# EncoderArm.net
KiCad netlist of a schematic drawn in Altium Designer
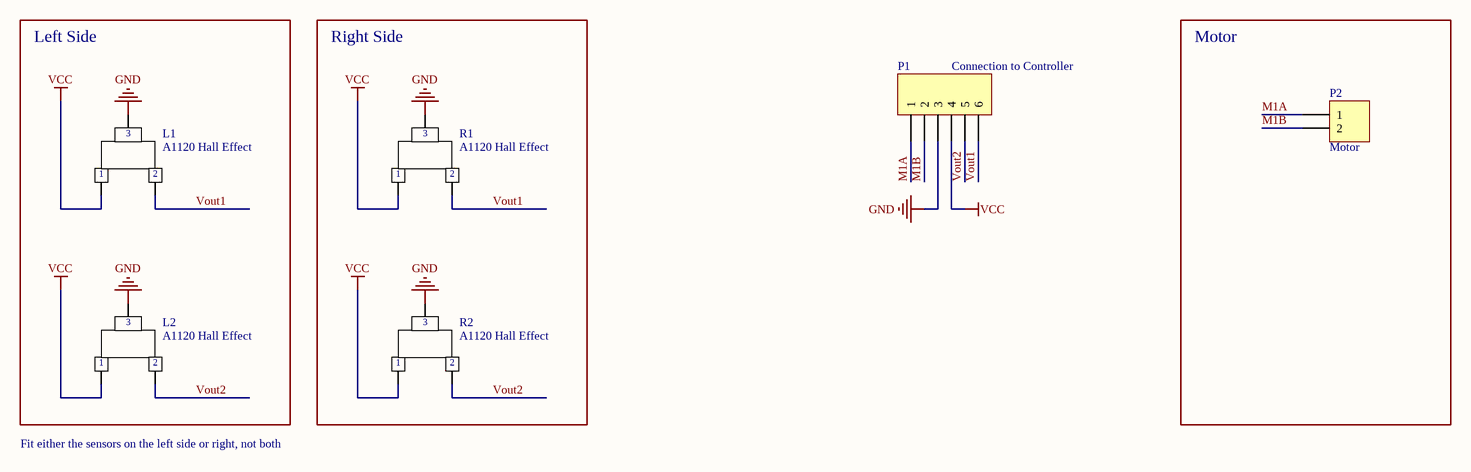
[diagram p0: EncoderArm.SchDoc]

(export (version "E")
  (design (tool "Eeschema 10.0.6"))
  (components
    (comp (ref "L1")
      (value "A1120 Hall Effect")
      (footprint "SOT23-3N")
      (libsource (lib "QUT") (part "FT_SOT23-3"))
    )
    (comp (ref "L2")
      (value "A1120 Hall Effect")
      (footprint "SOT23-3N")
      (libsource (lib "QUT") (part "FT_SOT23-3"))
    )
    (comp (ref "P1")
      (value "Connection to Controller")
      (footprint "HDR1X6")
      (description "Header, 6-Pin")
      (fields (field (name "PUBLISHER") "Altium Limited"))
      (libsource (lib "Miscellaneous Connectors") (part "Header 6"))
    )
    (comp (ref "P2")
      (value "Motor")
      (footprint "HDR1X2")
      (description "Header, 2-Pin")
      (fields (field (name "PUBLISHER") "Altium Limited"))
      (libsource (lib "Miscellaneous Connectors") (part "Header 2"))
    )
    (comp (ref "R1")
      (value "A1120 Hall Effect")
      (footprint "SOT23-3N")
      (libsource (lib "QUT") (part "FT_SOT23-3"))
    )
    (comp (ref "R2")
      (value "A1120 Hall Effect")
      (footprint "SOT23-3N")
      (libsource (lib "QUT") (part "FT_SOT23-3"))
    )
  )
  (nets
    (net (code "1") (name "/M1A") (class "Default")
      (node (ref "P1") (pin "1") (pinfunction "1_1") (pintype "passive"))
      (node (ref "P2") (pin "1") (pinfunction "1_1") (pintype "passive"))
    )
    (net (code "2") (name "/M1B") (class "Default")
      (node (ref "P1") (pin "2") (pinfunction "2_2") (pintype "passive"))
      (node (ref "P2") (pin "2") (pinfunction "2_2") (pintype "passive"))
    )
    (net (code "3") (name "/Vout1") (class "Default")
      (node (ref "L1") (pin "2") (pinfunction "2_2") (pintype "passive"))
      (node (ref "P1") (pin "6") (pinfunction "6_6") (pintype "passive"))
      (node (ref "R1") (pin "2") (pinfunction "2_2") (pintype "passive"))
    )
    (net (code "4") (name "/Vout2") (class "Default")
      (node (ref "L2") (pin "2") (pinfunction "2_2") (pintype "passive"))
      (node (ref "P1") (pin "5") (pinfunction "5_5") (pintype "passive"))
      (node (ref "R2") (pin "2") (pinfunction "2_2") (pintype "passive"))
    )
    (net (code "5") (name "GND") (class "Default")
      (node (ref "L1") (pin "3") (pinfunction "3_3") (pintype "passive"))
      (node (ref "L2") (pin "3") (pinfunction "3_3") (pintype "passive"))
      (node (ref "P1") (pin "3") (pinfunction "3_3") (pintype "passive"))
      (node (ref "R1") (pin "3") (pinfunction "3_3") (pintype "passive"))
      (node (ref "R2") (pin "3") (pinfunction "3_3") (pintype "passive"))
    )
    (net (code "6") (name "VCC") (class "Default")
      (node (ref "L1") (pin "1") (pinfunction "1_1") (pintype "passive"))
      (node (ref "L2") (pin "1") (pinfunction "1_1") (pintype "passive"))
      (node (ref "P1") (pin "4") (pinfunction "4_4") (pintype "passive"))
      (node (ref "R1") (pin "1") (pinfunction "1_1") (pintype "passive"))
      (node (ref "R2") (pin "1") (pinfunction "1_1") (pintype "passive"))
    )
  )
)
